# schematic.net
KiCad netlist of a schematic drawn in EAGLE
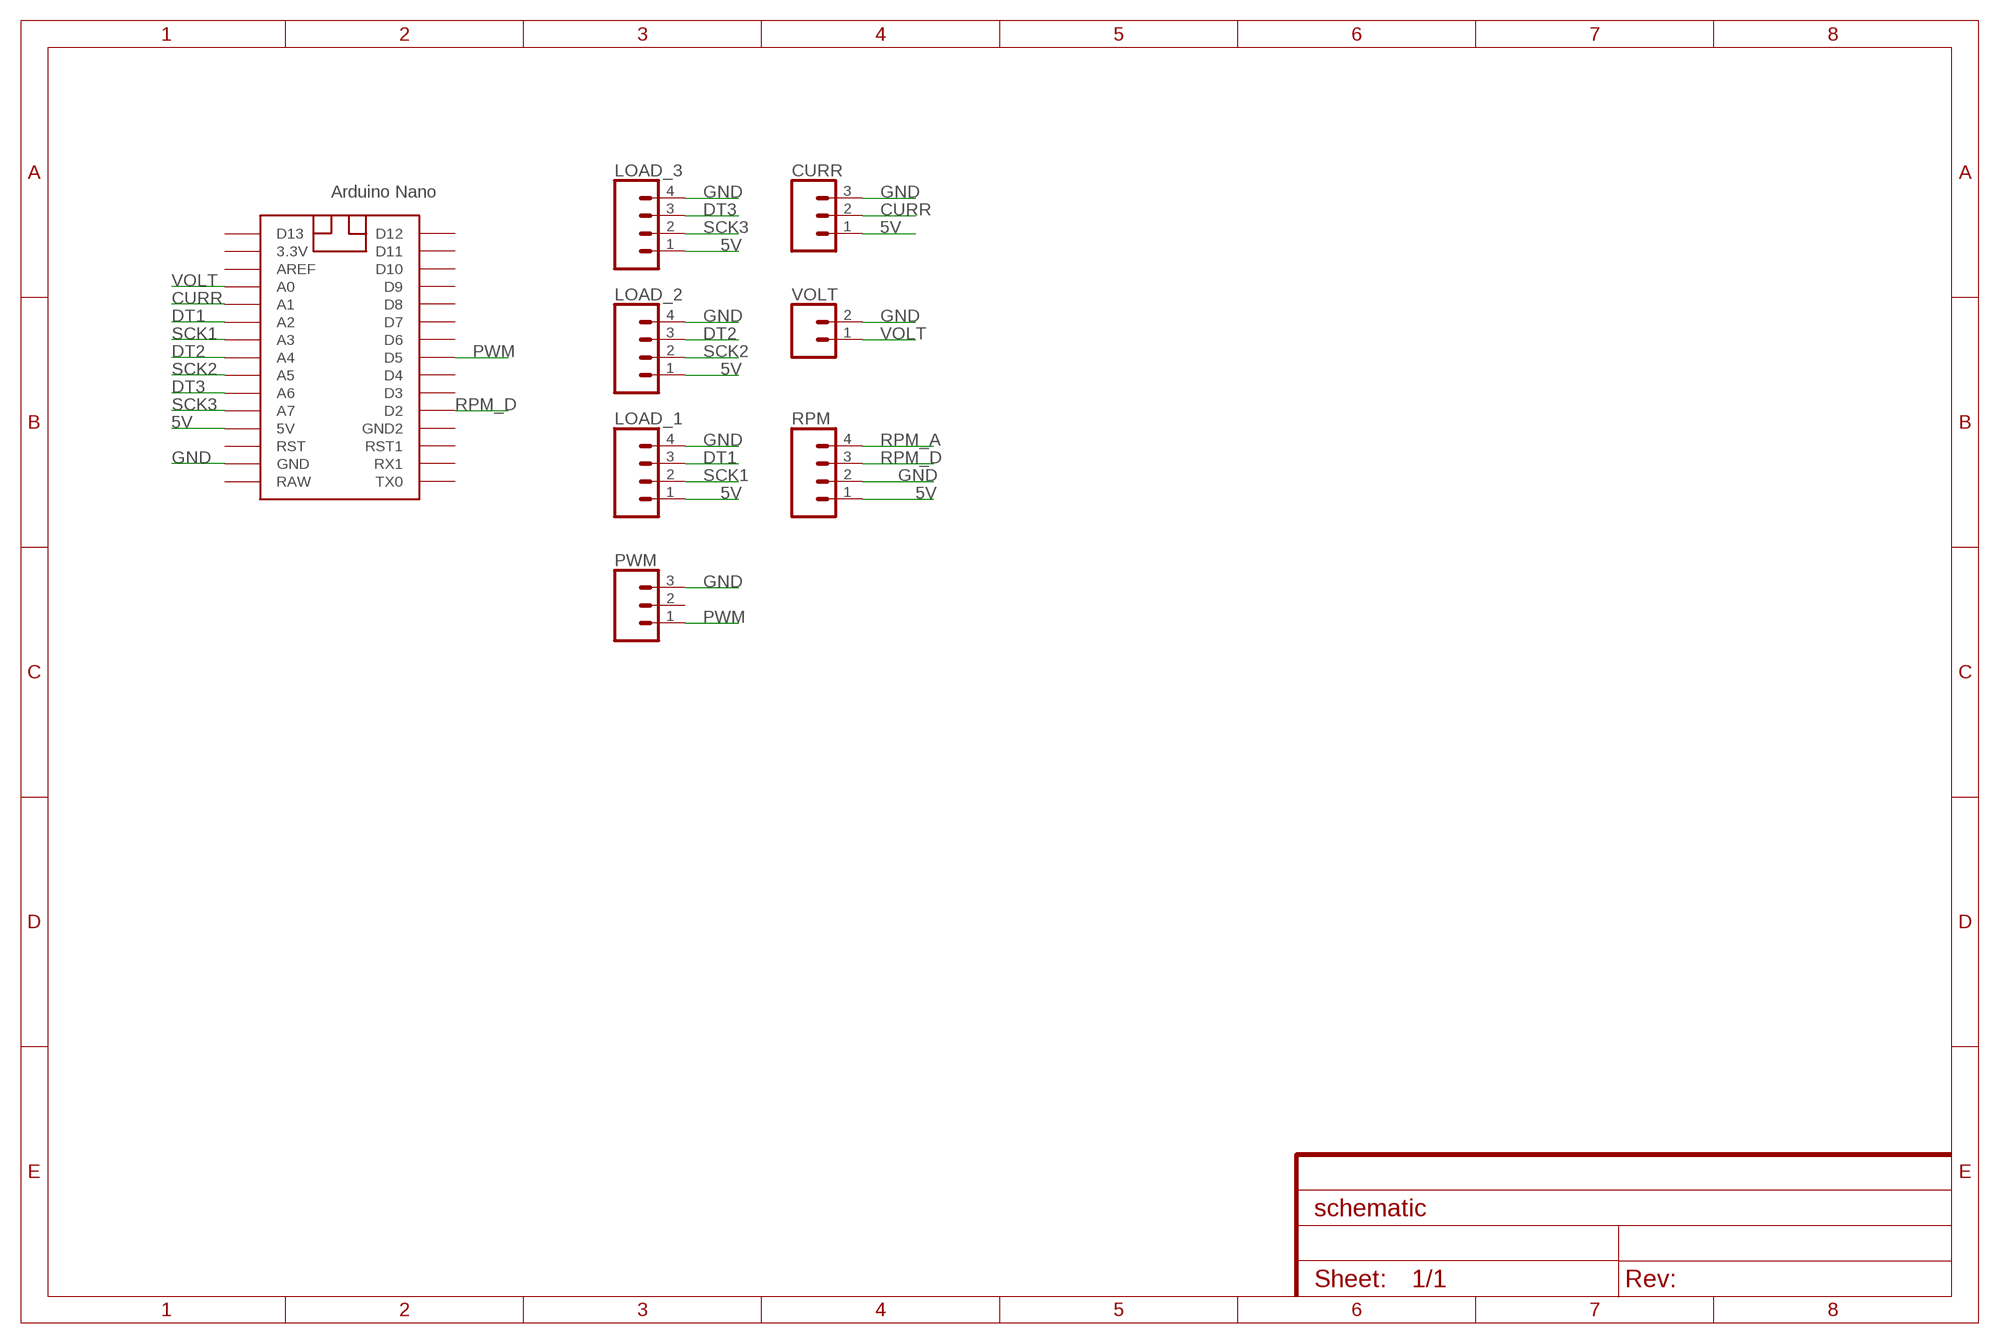
[diagram p0: schematic, sheet 1]

(export (version "E")
  (design (tool "Eeschema 10.0.6"))
  (components
    (comp (ref "CURR")
      (value "CONN_03POLAR")
      (footprint "eagle-import:MOLEX-1X3")
      (libsource (lib "eagle-import") (part "CONN_03POLAR"))
    )
    (comp (ref "LOAD_1")
      (value "CONN_04POLAR")
      (footprint "eagle-import:MOLEX-1X4")
      (libsource (lib "eagle-import") (part "CONN_04POLAR"))
    )
    (comp (ref "LOAD_2")
      (value "CONN_04POLAR")
      (footprint "eagle-import:MOLEX-1X4")
      (libsource (lib "eagle-import") (part "CONN_04POLAR"))
    )
    (comp (ref "LOAD_3")
      (value "CONN_04POLAR")
      (footprint "eagle-import:MOLEX-1X4")
      (libsource (lib "eagle-import") (part "CONN_04POLAR"))
    )
    (comp (ref "PWM")
      (value "CONN_03POLAR")
      (footprint "eagle-import:MOLEX-1X3")
      (libsource (lib "eagle-import") (part "SparkFun-Connectors_513_CONN_03POLAR"))
    )
    (comp (ref "RPM")
      (value "CONN_04POLAR")
      (footprint "eagle-import:MOLEX-1X4")
      (libsource (lib "eagle-import") (part "CONN_04POLAR"))
    )
    (comp (ref "U$1")
      (value "NANO")
      (footprint "eagle-import:NANO")
      (libsource (lib "eagle-import") (part "NANO"))
    )
    (comp (ref "VOLT")
      (value "CONN_02POLAR")
      (footprint "eagle-import:MOLEX-1X2")
      (libsource (lib "eagle-import") (part "CONN_02POLAR"))
    )
  )
  (nets
    (net (code "1") (name "/5V") (class "Default")
      (node (ref "CURR") (pin "1") (pinfunction "1_1") (pintype "passive"))
      (node (ref "LOAD_1") (pin "1") (pinfunction "1_1") (pintype "passive"))
      (node (ref "LOAD_2") (pin "1") (pinfunction "1_1") (pintype "passive"))
      (node (ref "LOAD_3") (pin "1") (pinfunction "1_1") (pintype "passive"))
      (node (ref "RPM") (pin "1") (pinfunction "1_1") (pintype "passive"))
      (node (ref "U$1") (pin "5V") (pinfunction "5V_5V") (pintype "bidirectional"))
    )
    (net (code "2") (name "/CURR") (class "Default")
      (node (ref "CURR") (pin "2") (pinfunction "2_2") (pintype "passive"))
      (node (ref "U$1") (pin "A1") (pinfunction "A1_A1") (pintype "bidirectional"))
    )
    (net (code "3") (name "/DT1") (class "Default")
      (node (ref "LOAD_1") (pin "3") (pinfunction "3_3") (pintype "passive"))
      (node (ref "U$1") (pin "A2") (pinfunction "A2_A2") (pintype "bidirectional"))
    )
    (net (code "4") (name "/DT2") (class "Default")
      (node (ref "LOAD_2") (pin "3") (pinfunction "3_3") (pintype "passive"))
      (node (ref "U$1") (pin "A4") (pinfunction "A4_A4") (pintype "bidirectional"))
    )
    (net (code "5") (name "/DT3") (class "Default")
      (node (ref "LOAD_3") (pin "3") (pinfunction "3_3") (pintype "passive"))
      (node (ref "U$1") (pin "A6") (pinfunction "A6_A6") (pintype "bidirectional"))
    )
    (net (code "6") (name "/GND") (class "Default")
      (node (ref "CURR") (pin "3") (pinfunction "3_3") (pintype "passive"))
      (node (ref "LOAD_1") (pin "4") (pinfunction "4_4") (pintype "passive"))
      (node (ref "LOAD_2") (pin "4") (pinfunction "4_4") (pintype "passive"))
      (node (ref "LOAD_3") (pin "4") (pinfunction "4_4") (pintype "passive"))
      (node (ref "PWM") (pin "3") (pinfunction "3_3") (pintype "passive"))
      (node (ref "RPM") (pin "2") (pinfunction "2_2") (pintype "passive"))
      (node (ref "U$1") (pin "GND") (pinfunction "GND_GND") (pintype "bidirectional"))
      (node (ref "VOLT") (pin "2") (pinfunction "2_2") (pintype "passive"))
    )
    (net (code "7") (name "/PWM") (class "Default")
      (node (ref "PWM") (pin "1") (pinfunction "1_1") (pintype "passive"))
      (node (ref "U$1") (pin "D5") (pinfunction "D5_D5") (pintype "bidirectional"))
    )
    (net (code "8") (name "/RPM_A") (class "Default")
      (node (ref "RPM") (pin "4") (pinfunction "4_4") (pintype "passive"))
    )
    (net (code "9") (name "/RPM_D") (class "Default")
      (node (ref "RPM") (pin "3") (pinfunction "3_3") (pintype "passive"))
      (node (ref "U$1") (pin "D2") (pinfunction "D2_D2") (pintype "bidirectional"))
    )
    (net (code "10") (name "/SCK1") (class "Default")
      (node (ref "LOAD_1") (pin "2") (pinfunction "2_2") (pintype "passive"))
      (node (ref "U$1") (pin "A3") (pinfunction "A3_A3") (pintype "bidirectional"))
    )
    (net (code "11") (name "/SCK2") (class "Default")
      (node (ref "LOAD_2") (pin "2") (pinfunction "2_2") (pintype "passive"))
      (node (ref "U$1") (pin "A5") (pinfunction "A5_A5") (pintype "bidirectional"))
    )
    (net (code "12") (name "/SCK3") (class "Default")
      (node (ref "LOAD_3") (pin "2") (pinfunction "2_2") (pintype "passive"))
      (node (ref "U$1") (pin "A7") (pinfunction "A7_A7") (pintype "bidirectional"))
    )
    (net (code "13") (name "/VOLT") (class "Default")
      (node (ref "U$1") (pin "A0") (pinfunction "A0_A0") (pintype "bidirectional"))
      (node (ref "VOLT") (pin "1") (pinfunction "1_1") (pintype "passive"))
    )
    (net (code "14") (name "unconnected-(PWM-Pad2)") (class "Default")
      (node (ref "PWM") (pin "2") (pinfunction "2_2") (pintype "passive"))
    )
    (net (code "15") (name "unconnected-(U$1-GND2-PadGND1)") (class "Default")
      (node (ref "U$1") (pin "GND1") (pinfunction "GND2_GND1") (pintype "bidirectional"))
    )
    (net (code "16") (name "unconnected-(U$1-Pad3.3V)") (class "Default")
      (node (ref "U$1") (pin "3.3V") (pinfunction "3.3V_3.3V") (pintype "bidirectional"))
    )
    (net (code "17") (name "unconnected-(U$1-PadAREF)") (class "Default")
      (node (ref "U$1") (pin "AREF") (pinfunction "AREF_AREF") (pintype "bidirectional"))
    )
    (net (code "18") (name "unconnected-(U$1-PadD3)") (class "Default")
      (node (ref "U$1") (pin "D3") (pinfunction "D3_D3") (pintype "bidirectional"))
    )
    (net (code "19") (name "unconnected-(U$1-PadD4)") (class "Default")
      (node (ref "U$1") (pin "D4") (pinfunction "D4_D4") (pintype "bidirectional"))
    )
    (net (code "20") (name "unconnected-(U$1-PadD6)") (class "Default")
      (node (ref "U$1") (pin "D6") (pinfunction "D6_D6") (pintype "bidirectional"))
    )
    (net (code "21") (name "unconnected-(U$1-PadD7)") (class "Default")
      (node (ref "U$1") (pin "D7") (pinfunction "D7_D7") (pintype "bidirectional"))
    )
    (net (code "22") (name "unconnected-(U$1-PadD8)") (class "Default")
      (node (ref "U$1") (pin "D8") (pinfunction "D8_D8") (pintype "bidirectional"))
    )
    (net (code "23") (name "unconnected-(U$1-PadD9)") (class "Default")
      (node (ref "U$1") (pin "D9") (pinfunction "D9_D9") (pintype "bidirectional"))
    )
    (net (code "24") (name "unconnected-(U$1-PadD10)") (class "Default")
      (node (ref "U$1") (pin "D10") (pinfunction "D10_D10") (pintype "bidirectional"))
    )
    (net (code "25") (name "unconnected-(U$1-PadD11)") (class "Default")
      (node (ref "U$1") (pin "D11") (pinfunction "D11_D11") (pintype "bidirectional"))
    )
    (net (code "26") (name "unconnected-(U$1-PadD12)") (class "Default")
      (node (ref "U$1") (pin "D12") (pinfunction "D12_D12") (pintype "bidirectional"))
    )
    (net (code "27") (name "unconnected-(U$1-PadD13)") (class "Default")
      (node (ref "U$1") (pin "D13") (pinfunction "D13_D13") (pintype "bidirectional"))
    )
    (net (code "28") (name "unconnected-(U$1-PadRAW)") (class "Default")
      (node (ref "U$1") (pin "RAW") (pinfunction "RAW_RAW") (pintype "bidirectional"))
    )
    (net (code "29") (name "unconnected-(U$1-PadRST)") (class "Default")
      (node (ref "U$1") (pin "RST") (pinfunction "RST_RST") (pintype "bidirectional"))
    )
    (net (code "30") (name "unconnected-(U$1-PadRST1)") (class "Default")
      (node (ref "U$1") (pin "RST1") (pinfunction "RST1_RST1") (pintype "bidirectional"))
    )
    (net (code "31") (name "unconnected-(U$1-PadRX1)") (class "Default")
      (node (ref "U$1") (pin "RX1") (pinfunction "RX1_RX1") (pintype "bidirectional"))
    )
    (net (code "32") (name "unconnected-(U$1-PadTX0)") (class "Default")
      (node (ref "U$1") (pin "TX0") (pinfunction "TX0_TX0") (pintype "bidirectional"))
    )
  )
)
